# fpga-bank8.net
KiCad netlist of a schematic drawn in Altium Designer
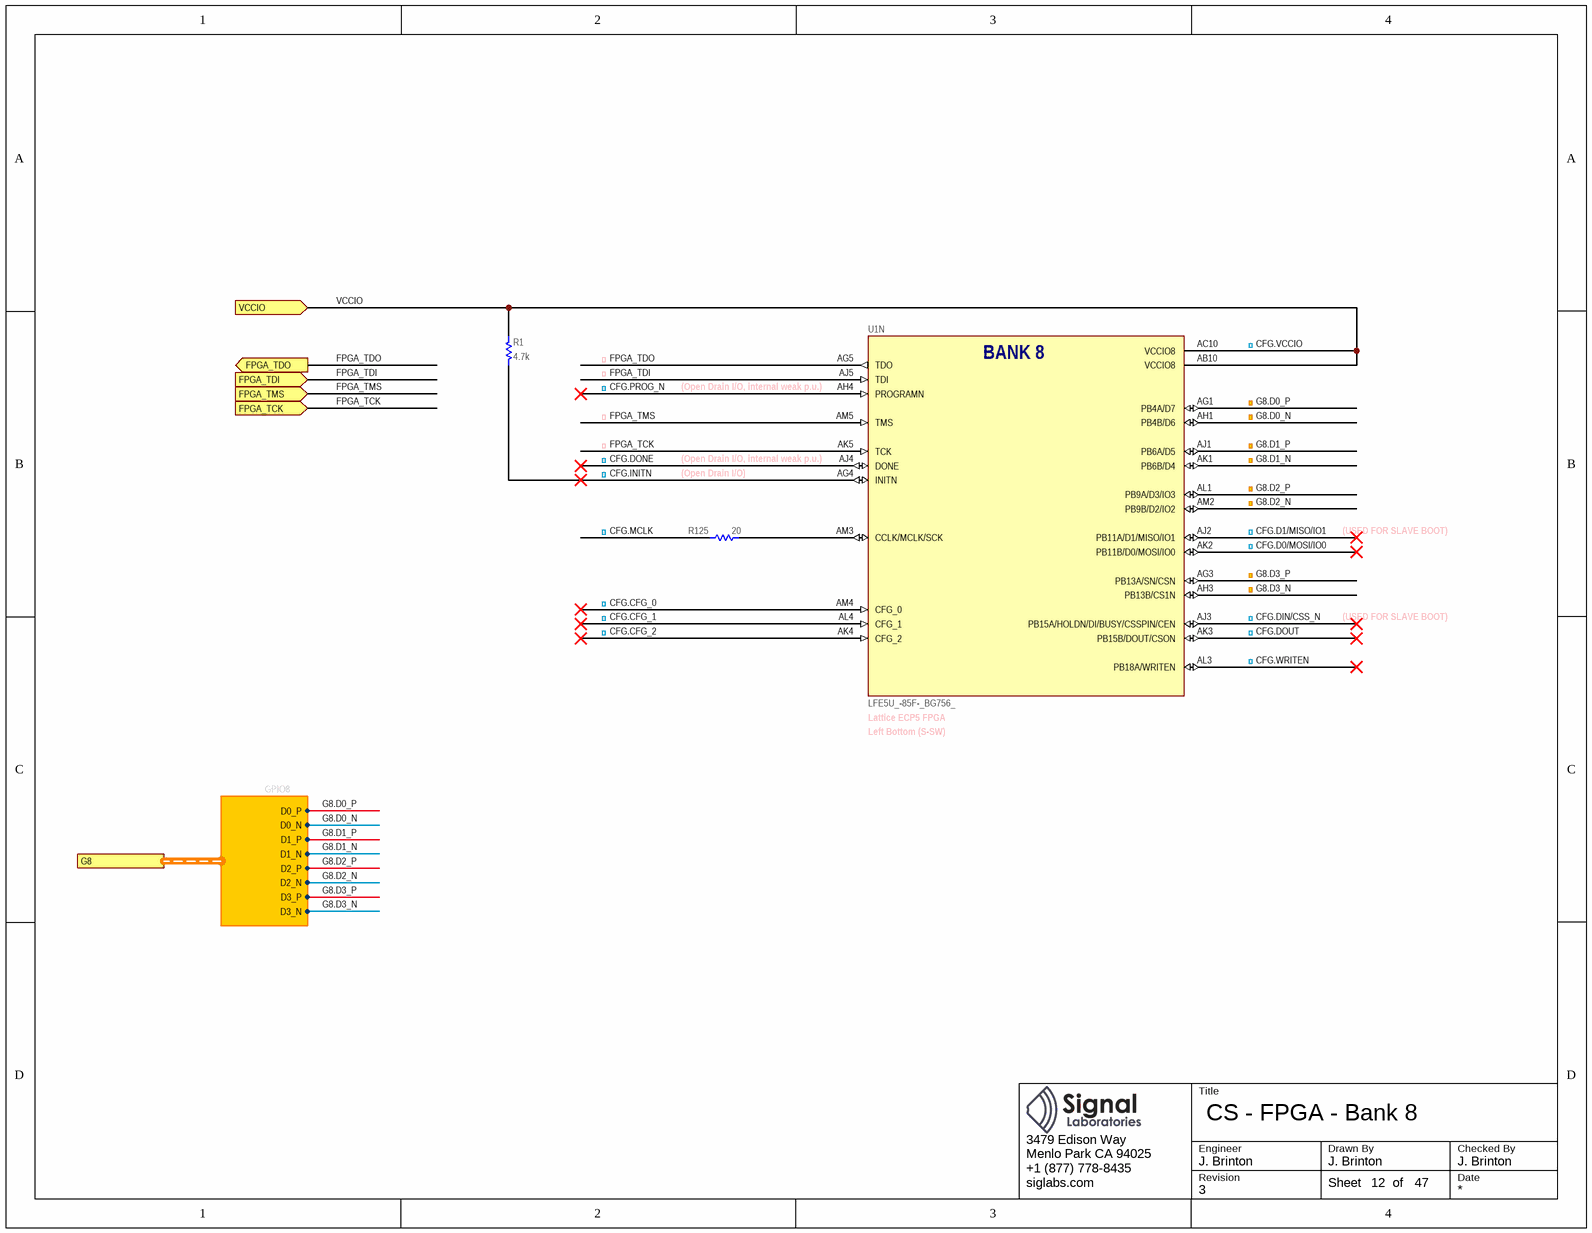
[diagram p0: fpga-bank8.SchDoc]

(export (version "E")
  (design (tool "Eeschema 10.0.6"))
  (components
    (comp (ref "R1")
      (value "4.7k")
      (footprint "RESC1005X40N")
      (description "Thick Film Resistor 4.7k ±1% 0.1W 75V 0402")
      (fields (field (name "TOLERANCE") "±1%") (field (name "MANUFACTURER") "Panasonic"))
      (libsource (lib "generic") (part "RES"))
    )
    (comp (ref "R125")
      (value "20")
      (footprint "RESC1005X40N")
      (description "Thick Film Resistor 20 ±1% 0.1W 75V 0402")
      (fields (field (name "TOLERANCE") "±1%") (field (name "MANUFACTURER") "Panasonic"))
      (libsource (lib "generic") (part "RES"))
    )
    (comp (ref "U1")
      (value "LFE5U_-85F-_BG756_")
      (footprint "lattice:caBGA756")
      (description "ECP5 FPGA, 85k LUT, 756-caBGA")
      (fields (field (name "MANUFACTURER") "Lattice Semiconductor"))
      (libsource (lib "lattice") (part "LFE5U_-85F-_BG756_"))
    )
  )
  (nets
    (net (code "2") (name "/CFG.CFG_0") (class "Default")
      (node (ref "U1") (pin "AM4") (pinfunction "CFG_0_AM4") (pintype "input+no_connect"))
    )
    (net (code "3") (name "/CFG.CFG_1") (class "Default")
      (node (ref "U1") (pin "AL4") (pinfunction "CFG_1_AL4") (pintype "input+no_connect"))
    )
    (net (code "4") (name "/CFG.CFG_2") (class "Default")
      (node (ref "U1") (pin "AK4") (pinfunction "CFG_2_AK4") (pintype "input+no_connect"))
    )
    (net (code "5") (name "/CFG.D0{slash}MOSI{slash}IO0") (class "Default")
      (node (ref "U1") (pin "AK2") (pinfunction "PB11B/D0/MOSI/IO0_AK2") (pintype "bidirectional+no_connect"))
    )
    (net (code "6") (name "/CFG.D1{slash}MISO{slash}IO1") (class "Default")
      (node (ref "U1") (pin "AJ2") (pinfunction "PB11A/D1/MISO/IO1_AJ2") (pintype "bidirectional+no_connect"))
    )
    (net (code "7") (name "/CFG.DIN{slash}CSS_N") (class "Default")
      (node (ref "U1") (pin "AJ3") (pinfunction "PB15A/HOLDN/DI/BUSY/CSSPIN/CEN_AJ3") (pintype "bidirectional+no_connect"))
    )
    (net (code "8") (name "/CFG.DONE") (class "Default")
      (node (ref "U1") (pin "AJ4") (pinfunction "DONE_AJ4") (pintype "bidirectional+no_connect"))
    )
    (net (code "9") (name "/CFG.DOUT") (class "Default")
      (node (ref "U1") (pin "AK3") (pinfunction "PB15B/DOUT/CSON_AK3") (pintype "bidirectional+no_connect"))
    )
    (net (code "10") (name "/CFG.INITN") (class "Default")
      (node (ref "R1") (pin "1") (pinfunction "1_1") (pintype "passive"))
      (node (ref "U1") (pin "AG4") (pinfunction "INITN_AG4") (pintype "bidirectional"))
    )
    (net (code "11") (name "/CFG.MCLK") (class "Default")
      (node (ref "R125") (pin "1") (pinfunction "1_1") (pintype "passive"))
    )
    (net (code "12") (name "/CFG.PROG_N") (class "Default")
      (node (ref "U1") (pin "AH4") (pinfunction "PROGRAMN_AH4") (pintype "input+no_connect"))
    )
    (net (code "13") (name "/CFG.VCCIO") (class "Default")
      (node (ref "R1") (pin "2") (pinfunction "2_2") (pintype "passive"))
      (node (ref "U1") (pin "AB10") (pinfunction "VCCIO8_AB10") (pintype "power_in"))
      (node (ref "U1") (pin "AC10") (pinfunction "VCCIO8_AC10") (pintype "power_in"))
    )
    (net (code "14") (name "/CFG.WRITEN") (class "Default")
      (node (ref "U1") (pin "AL3") (pinfunction "PB18A/WRITEN_AL3") (pintype "bidirectional+no_connect"))
    )
    (net (code "15") (name "/FPGA_TCK") (class "Default")
      (node (ref "U1") (pin "AK5") (pinfunction "TCK_AK5") (pintype "input"))
    )
    (net (code "16") (name "/FPGA_TDI") (class "Default")
      (node (ref "U1") (pin "AJ5") (pinfunction "TDI_AJ5") (pintype "input"))
    )
    (net (code "17") (name "/FPGA_TDO") (class "Default")
      (node (ref "U1") (pin "AG5") (pinfunction "TDO_AG5") (pintype "output"))
    )
    (net (code "18") (name "/FPGA_TMS") (class "Default")
      (node (ref "U1") (pin "AM5") (pinfunction "TMS_AM5") (pintype "input"))
    )
    (net (code "19") (name "/G8.D0_N") (class "Default")
      (node (ref "U1") (pin "AH1") (pinfunction "PB4B/D6_AH1") (pintype "bidirectional"))
    )
    (net (code "20") (name "/G8.D0_P") (class "Default")
      (node (ref "U1") (pin "AG1") (pinfunction "PB4A/D7_AG1") (pintype "bidirectional"))
    )
    (net (code "21") (name "/G8.D1_N") (class "Default")
      (node (ref "U1") (pin "AK1") (pinfunction "PB6B/D4_AK1") (pintype "bidirectional"))
    )
    (net (code "22") (name "/G8.D1_P") (class "Default")
      (node (ref "U1") (pin "AJ1") (pinfunction "PB6A/D5_AJ1") (pintype "bidirectional"))
    )
    (net (code "23") (name "/G8.D2_N") (class "Default")
      (node (ref "U1") (pin "AM2") (pinfunction "PB9B/D2/IO2_AM2") (pintype "bidirectional"))
    )
    (net (code "24") (name "/G8.D2_P") (class "Default")
      (node (ref "U1") (pin "AL1") (pinfunction "PB9A/D3/IO3_AL1") (pintype "bidirectional"))
    )
    (net (code "25") (name "/G8.D3_N") (class "Default")
      (node (ref "U1") (pin "AH3") (pinfunction "PB13B/CS1N_AH3") (pintype "bidirectional"))
    )
    (net (code "26") (name "/G8.D3_P") (class "Default")
      (node (ref "U1") (pin "AG3") (pinfunction "PB13A/SN/CSN_AG3") (pintype "bidirectional"))
    )
    (net (code "28") (name "Net-(U1N-CCLK{slash}MCLK{slash}SCK)") (class "Default")
      (node (ref "R125") (pin "2") (pinfunction "2_2") (pintype "passive"))
      (node (ref "U1") (pin "AM3") (pinfunction "CCLK/MCLK/SCK_AM3") (pintype "bidirectional"))
    )
  )
)
